# TemperatureMon.net
KiCad netlist of a schematic drawn in Altium Designer
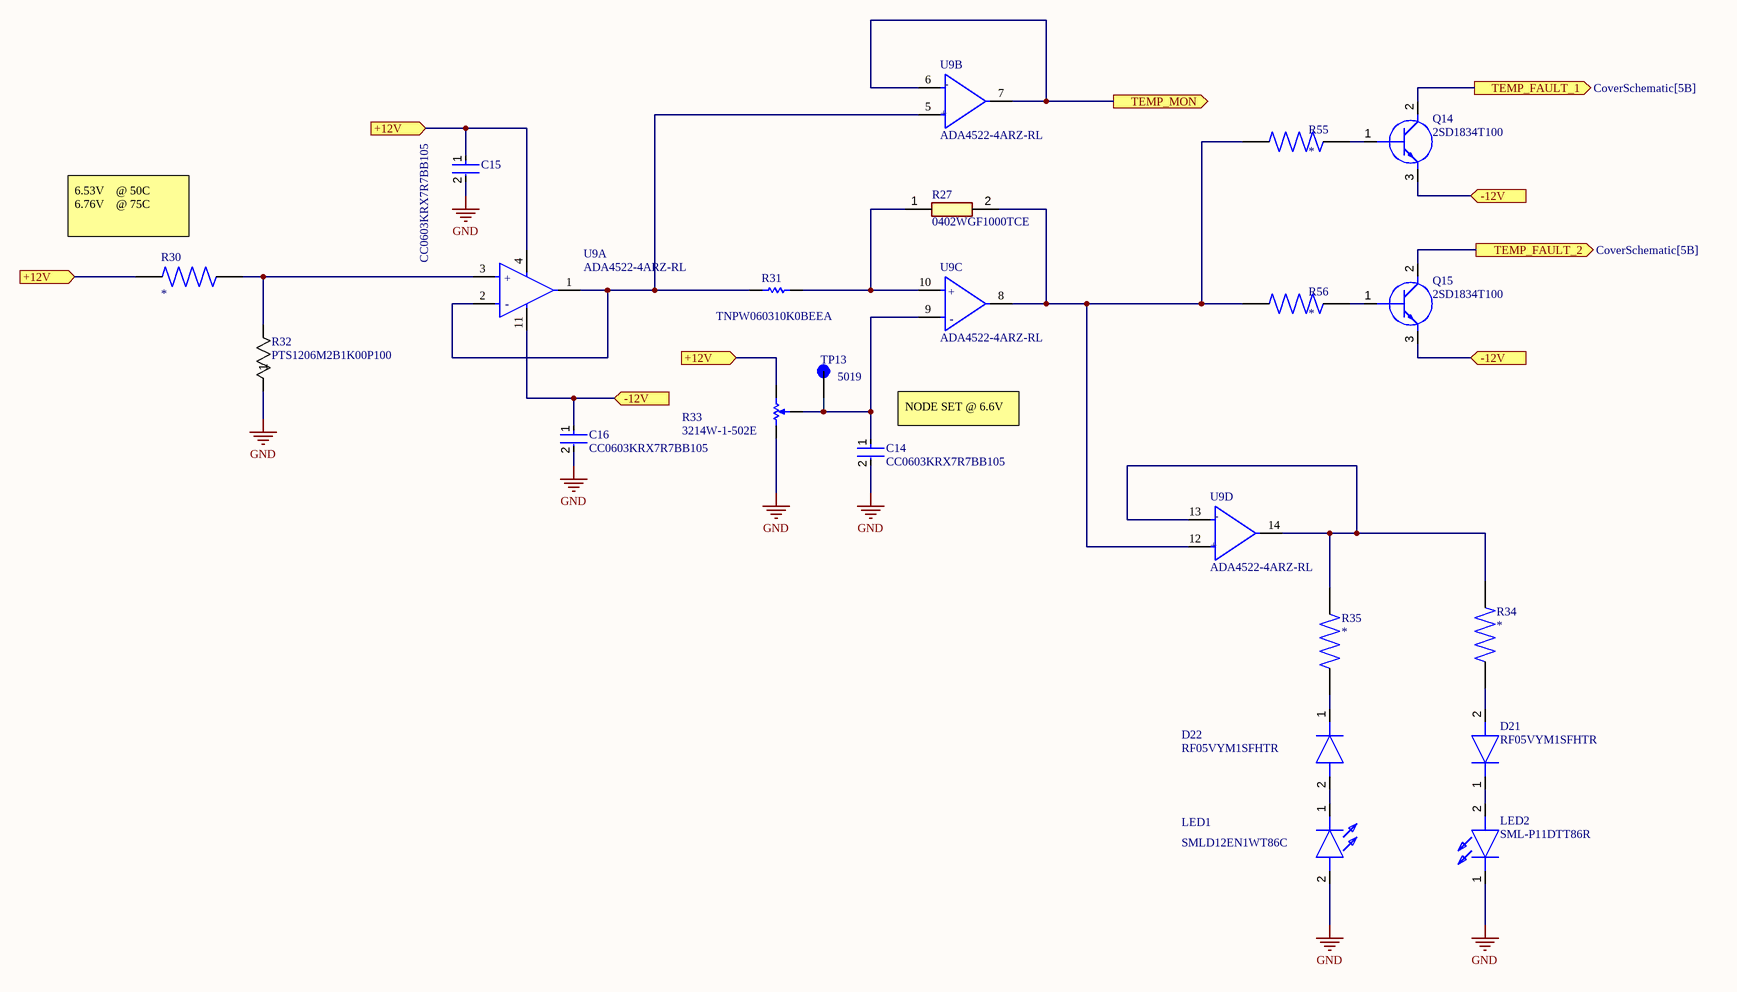
[diagram p0: TemperatureMon.SchDoc]

(export (version "E")
  (design (tool "Eeschema 10.0.6"))
  (components
    (comp (ref "C14")
      (value "CC0603KRX7R7BB105")
      (footprint "FP-CC0603-DA-MFG")
      (description "CAP CER 1UF 16V X7R 0603")
      (fields (field (name "TOLERANCE") "0.1") (field (name "MANUFACTURER") "YAGEO"))
      (libsource (lib "Altium Content Vault") (part "11868f565c42a9108669ba33697ecf6"))
    )
    (comp (ref "C15")
      (value "CC0603KRX7R7BB105")
      (footprint "FP-CC0603-DA-MFG")
      (description "CAP CER 1UF 16V X7R 0603")
      (fields (field (name "TOLERANCE") "0.1") (field (name "MANUFACTURER") "YAGEO"))
      (libsource (lib "Altium Content Vault") (part "11868f565c42a9108669ba33697ecf6"))
    )
    (comp (ref "C16")
      (value "CC0603KRX7R7BB105")
      (footprint "FP-CC0603-DA-MFG")
      (description "CAP CER 1UF 16V X7R 0603")
      (fields (field (name "TOLERANCE") "0.1") (field (name "MANUFACTURER") "YAGEO"))
      (libsource (lib "Altium Content Vault") (part "11868f565c42a9108669ba33697ecf6"))
    )
    (comp (ref "D21")
      (value "RF05VYM1SFHTR")
      (footprint "SamacSys:RF05VYM1SFHTR")
      (description "Diode")
      (fields (field (name "MOUSER PART NUMBER") "755-RF05VYM1SFHTR"))
      (libsource (lib "*") (part "RF05VYM1SFHTR"))
    )
    (comp (ref "D22")
      (value "RF05VYM1SFHTR")
      (footprint "SamacSys:RF05VYM1SFHTR")
      (description "Diode")
      (fields (field (name "MOUSER PART NUMBER") "755-RF05VYM1SFHTR"))
      (libsource (lib "*") (part "RF05VYM1SFHTR"))
    )
    (comp (ref "LED1")
      (value "SMLD12EN1WT86C")
      (footprint "SamacSys:SMLD12EN1WT86C")
      (description "LED")
      (fields (field (name "MOUSER PART NUMBER") "755-SMLD12EN1WT86C"))
      (libsource (lib "*") (part "SMLD12EN1WT86C"))
    )
    (comp (ref "LED2")
      (value "SML-P11DTT86R")
      (footprint "SamacSys:SML-P11(1X0.6)")
      (description "LED")
      (fields (field (name "MOUSER PART NUMBER") "755-SML-P11DTT86R"))
      (libsource (lib "*") (part "SML-P11DTT86R"))
    )
    (comp (ref "Q14")
      (value "2SD1834T100")
      (footprint "SamacSys:RJP020N06")
      (description "Transistor BJT NPN")
      (fields (field (name "MOUSER PART NUMBER") "755-2SD1834T100"))
      (libsource (lib "*") (part "2SD1834T100"))
    )
    (comp (ref "Q15")
      (value "2SD1834T100")
      (footprint "SamacSys:RJP020N06")
      (description "Transistor BJT NPN")
      (fields (field (name "MOUSER PART NUMBER") "755-2SD1834T100"))
      (libsource (lib "*") (part "2SD1834T100"))
    )
    (comp (ref "R27")
      (value "0402WGF1000TCE")
      (footprint "SamacSys:RESC1005X40N")
      (description "Resistor")
      (libsource (lib "*") (part "0402WGF1000TCE"))
    )
    (comp (ref "R30")
      (value "MCT06030C1001FP500")
      (footprint "MCT06030C1001FP500:RESC1508X55N")
      (description "Res Thin Film 0603 1K Ohm 1% 0.1W(1/10W) ?50ppm/C Molded SMD Automotive Medical T/R")
      (fields (field (name "ALTIUM_VALUE") "*") (field (name "MF") "{'manufacturer': u'Vishay Beyschlag'}"))
      (libsource (lib "MCT06030C1001FP500") (part "MCT06030C1001FP500"))
    )
    (comp (ref "R31")
      (value "TNPW060310K0BEEA")
      (footprint "RESC1609X55X30NL10T20")
      (fields (field (name "MANUFACTURER") "Vishay Dale"))
      (libsource (lib "Altium Content Vault") (part "RES"))
    )
    (comp (ref "R32")
      (value "PTS1206M2B1K00P100")
      (footprint "PTS 1206_VIS")
      (description "No Description Available")
      (libsource (lib "PTS1206M2B1K00P100") (part "PTS1206M2B1K00P100"))
    )
    (comp (ref "R33")
      (value "3214W-1-502E")
      (footprint "BOUR-3214W_V")
      (fields (field (name "MANUFACTURER") "Bourns"))
      (libsource (lib "Altium Content Vault") (part "RES-ADJ-3_A"))
    )
    (comp (ref "R34")
      (value "MCT06030C1001FP500")
      (footprint "MCT06030C1001FP500:RESC1508X55N")
      (description "Res Thin Film 0603 1K Ohm 1% 0.1W(1/10W) ?50ppm/C Molded SMD Automotive Medical T/R")
      (fields (field (name "ALTIUM_VALUE") "*") (field (name "MF") "{'manufacturer': u'Vishay Beyschlag'}"))
      (libsource (lib "MCT06030C1001FP500") (part "MCT06030C1001FP500"))
    )
    (comp (ref "R35")
      (value "MCT06030C1001FP500")
      (footprint "MCT06030C1001FP500:RESC1508X55N")
      (description "Res Thin Film 0603 1K Ohm 1% 0.1W(1/10W) ?50ppm/C Molded SMD Automotive Medical T/R")
      (fields (field (name "ALTIUM_VALUE") "*") (field (name "MF") "{'manufacturer': u'Vishay Beyschlag'}"))
      (libsource (lib "MCT06030C1001FP500") (part "MCT06030C1001FP500"))
    )
    (comp (ref "R55")
      (value "MCT06030C1001FP500")
      (footprint "MCT06030C1001FP500:RESC1508X55N")
      (description "Res Thin Film 0603 1K Ohm 1% 0.1W(1/10W) ?50ppm/C Molded SMD Automotive Medical T/R")
      (fields (field (name "ALTIUM_VALUE") "*") (field (name "MF") "{'manufacturer': u'Vishay Beyschlag'}"))
      (libsource (lib "MCT06030C1001FP500") (part "MCT06030C1001FP500"))
    )
    (comp (ref "R56")
      (value "MCT06030C1001FP500")
      (footprint "MCT06030C1001FP500:RESC1508X55N")
      (description "Res Thin Film 0603 1K Ohm 1% 0.1W(1/10W) ?50ppm/C Molded SMD Automotive Medical T/R")
      (fields (field (name "ALTIUM_VALUE") "*") (field (name "MF") "{'manufacturer': u'Vishay Beyschlag'}"))
      (libsource (lib "MCT06030C1001FP500") (part "MCT06030C1001FP500"))
    )
    (comp (ref "TP13")
      (value "5019")
      (footprint "5019:KEYSTONE_5019")
      (fields (field (name "MF") "{'manufacturer': u'Keystone Electronics'}"))
      (libsource (lib "*") (part "5019"))
    )
    (comp (ref "U9")
      (value "ADA4522-4ARZ-RL")
      (footprint "FP-R-14-IPC_C")
      (description "IC OPAMP ZERO-DRIFT 4CIRC 14SOIC")
      (libsource (lib "Altium Content Vault") (part "684fa0f315d4229452f837ea2b10642"))
    )
  )
  (nets
    (net (code "1") (name "/+12V") (class "Default")
      (node (ref "C15") (pin "1") (pinfunction "1_1") (pintype "passive"))
      (node (ref "R30") (pin "2") (pinfunction "2_2") (pintype "passive"))
      (node (ref "R33") (pin "3") (pinfunction "3_3") (pintype "passive"))
      (node (ref "U9") (pin "4") (pinfunction "V+_4") (pintype "power_in"))
    )
    (net (code "2") (name "/-12V") (class "Default")
      (node (ref "C16") (pin "1") (pinfunction "1_1") (pintype "passive"))
      (node (ref "Q14") (pin "3") (pinfunction "E_3") (pintype "passive"))
      (node (ref "Q15") (pin "3") (pinfunction "E_3") (pintype "passive"))
      (node (ref "U9") (pin "11") (pinfunction "V-_11") (pintype "power_in"))
    )
    (net (code "3") (name "/TEMP_FAULT_1") (class "Default")
      (node (ref "Q14") (pin "2") (pinfunction "C_2") (pintype "passive"))
    )
    (net (code "4") (name "/TEMP_FAULT_2") (class "Default")
      (node (ref "Q15") (pin "2") (pinfunction "C_2") (pintype "passive"))
    )
    (net (code "5") (name "/TEMP_MON") (class "Default")
      (node (ref "U9") (pin "6") (pinfunction "-IN_B_6") (pintype "tri_state"))
      (node (ref "U9") (pin "7") (pinfunction "OUT_B_7") (pintype "passive"))
    )
    (net (code "6") (name "GND") (class "Default")
      (node (ref "C14") (pin "2") (pinfunction "2_2") (pintype "passive"))
      (node (ref "C15") (pin "2") (pinfunction "2_2") (pintype "passive"))
      (node (ref "C16") (pin "2") (pinfunction "2_2") (pintype "passive"))
      (node (ref "LED1") (pin "2") (pinfunction "A_2") (pintype "passive"))
      (node (ref "LED2") (pin "1") (pinfunction "K_1") (pintype "passive"))
      (node (ref "R32") (pin "1") (pinfunction "1_1") (pintype "passive"))
      (node (ref "R33") (pin "1") (pinfunction "1_1") (pintype "passive"))
    )
    (net (code "7") (name "Net-(D21-A)") (class "Default")
      (node (ref "D21") (pin "2") (pinfunction "A_2") (pintype "passive"))
      (node (ref "R34") (pin "2") (pinfunction "2_2") (pintype "passive"))
    )
    (net (code "8") (name "Net-(D21-K)") (class "Default")
      (node (ref "D21") (pin "1") (pinfunction "K_1") (pintype "passive"))
      (node (ref "LED2") (pin "2") (pinfunction "A_2") (pintype "passive"))
    )
    (net (code "9") (name "Net-(D22-A)") (class "Default")
      (node (ref "D22") (pin "2") (pinfunction "A_2") (pintype "passive"))
      (node (ref "LED1") (pin "1") (pinfunction "K_1") (pintype "passive"))
    )
    (net (code "10") (name "Net-(D22-K)") (class "Default")
      (node (ref "D22") (pin "1") (pinfunction "K_1") (pintype "passive"))
      (node (ref "R35") (pin "2") (pinfunction "2_2") (pintype "passive"))
    )
    (net (code "11") (name "Net-(Q14-B)") (class "Default")
      (node (ref "Q14") (pin "1") (pinfunction "B_1") (pintype "passive"))
      (node (ref "R55") (pin "2") (pinfunction "2_2") (pintype "passive"))
    )
    (net (code "12") (name "Net-(Q15-B)") (class "Default")
      (node (ref "Q15") (pin "1") (pinfunction "B_1") (pintype "passive"))
      (node (ref "R56") (pin "2") (pinfunction "2_2") (pintype "passive"))
    )
    (net (code "13") (name "Net-(U9A-+IN_A)") (class "Default")
      (node (ref "R30") (pin "1") (pinfunction "1_1") (pintype "passive"))
      (node (ref "R32") (pin "2") (pinfunction "2_2") (pintype "passive"))
      (node (ref "U9") (pin "3") (pinfunction "+IN_A_3") (pintype "tri_state"))
    )
    (net (code "14") (name "Net-(U9A--IN_A)") (class "Default")
      (node (ref "R31") (pin "1") (pinfunction "1_1") (pintype "passive"))
      (node (ref "U9") (pin "1") (pinfunction "OUT_A_1") (pintype "passive"))
      (node (ref "U9") (pin "2") (pinfunction "-IN_A_2") (pintype "tri_state"))
      (node (ref "U9") (pin "5") (pinfunction "+IN_B_5") (pintype "tri_state"))
    )
    (net (code "15") (name "Net-(U9C-+IN_C)") (class "Default")
      (node (ref "R27") (pin "1") (pinfunction "1_1") (pintype "passive"))
      (node (ref "R31") (pin "2") (pinfunction "2_2") (pintype "passive"))
      (node (ref "U9") (pin "10") (pinfunction "+IN_C_10") (pintype "tri_state"))
    )
    (net (code "16") (name "Net-(U9C--IN_C)") (class "Default")
      (node (ref "C14") (pin "1") (pinfunction "1_1") (pintype "passive"))
      (node (ref "R33") (pin "2") (pinfunction "2_2") (pintype "passive"))
      (node (ref "TP13") (pin "TP") (pinfunction "TP_TP") (pintype "passive"))
      (node (ref "U9") (pin "9") (pinfunction "-IN_C_9") (pintype "tri_state"))
    )
    (net (code "17") (name "Net-(U9C-OUT_C)") (class "Default")
      (node (ref "R27") (pin "2") (pinfunction "2_2") (pintype "passive"))
      (node (ref "R55") (pin "1") (pinfunction "1_1") (pintype "passive"))
      (node (ref "R56") (pin "1") (pinfunction "1_1") (pintype "passive"))
      (node (ref "U9") (pin "12") (pinfunction "+IN_D_12") (pintype "tri_state"))
      (node (ref "U9") (pin "8") (pinfunction "OUT_C_8") (pintype "passive"))
    )
    (net (code "18") (name "Net-(U9D--IN_D)") (class "Default")
      (node (ref "R34") (pin "1") (pinfunction "1_1") (pintype "passive"))
      (node (ref "R35") (pin "1") (pinfunction "1_1") (pintype "passive"))
      (node (ref "U9") (pin "13") (pinfunction "-IN_D_13") (pintype "tri_state"))
      (node (ref "U9") (pin "14") (pinfunction "OUT_D_14") (pintype "passive"))
    )
  )
)
